# CPLD.net
KiCad netlist of a schematic drawn in Altium Designer
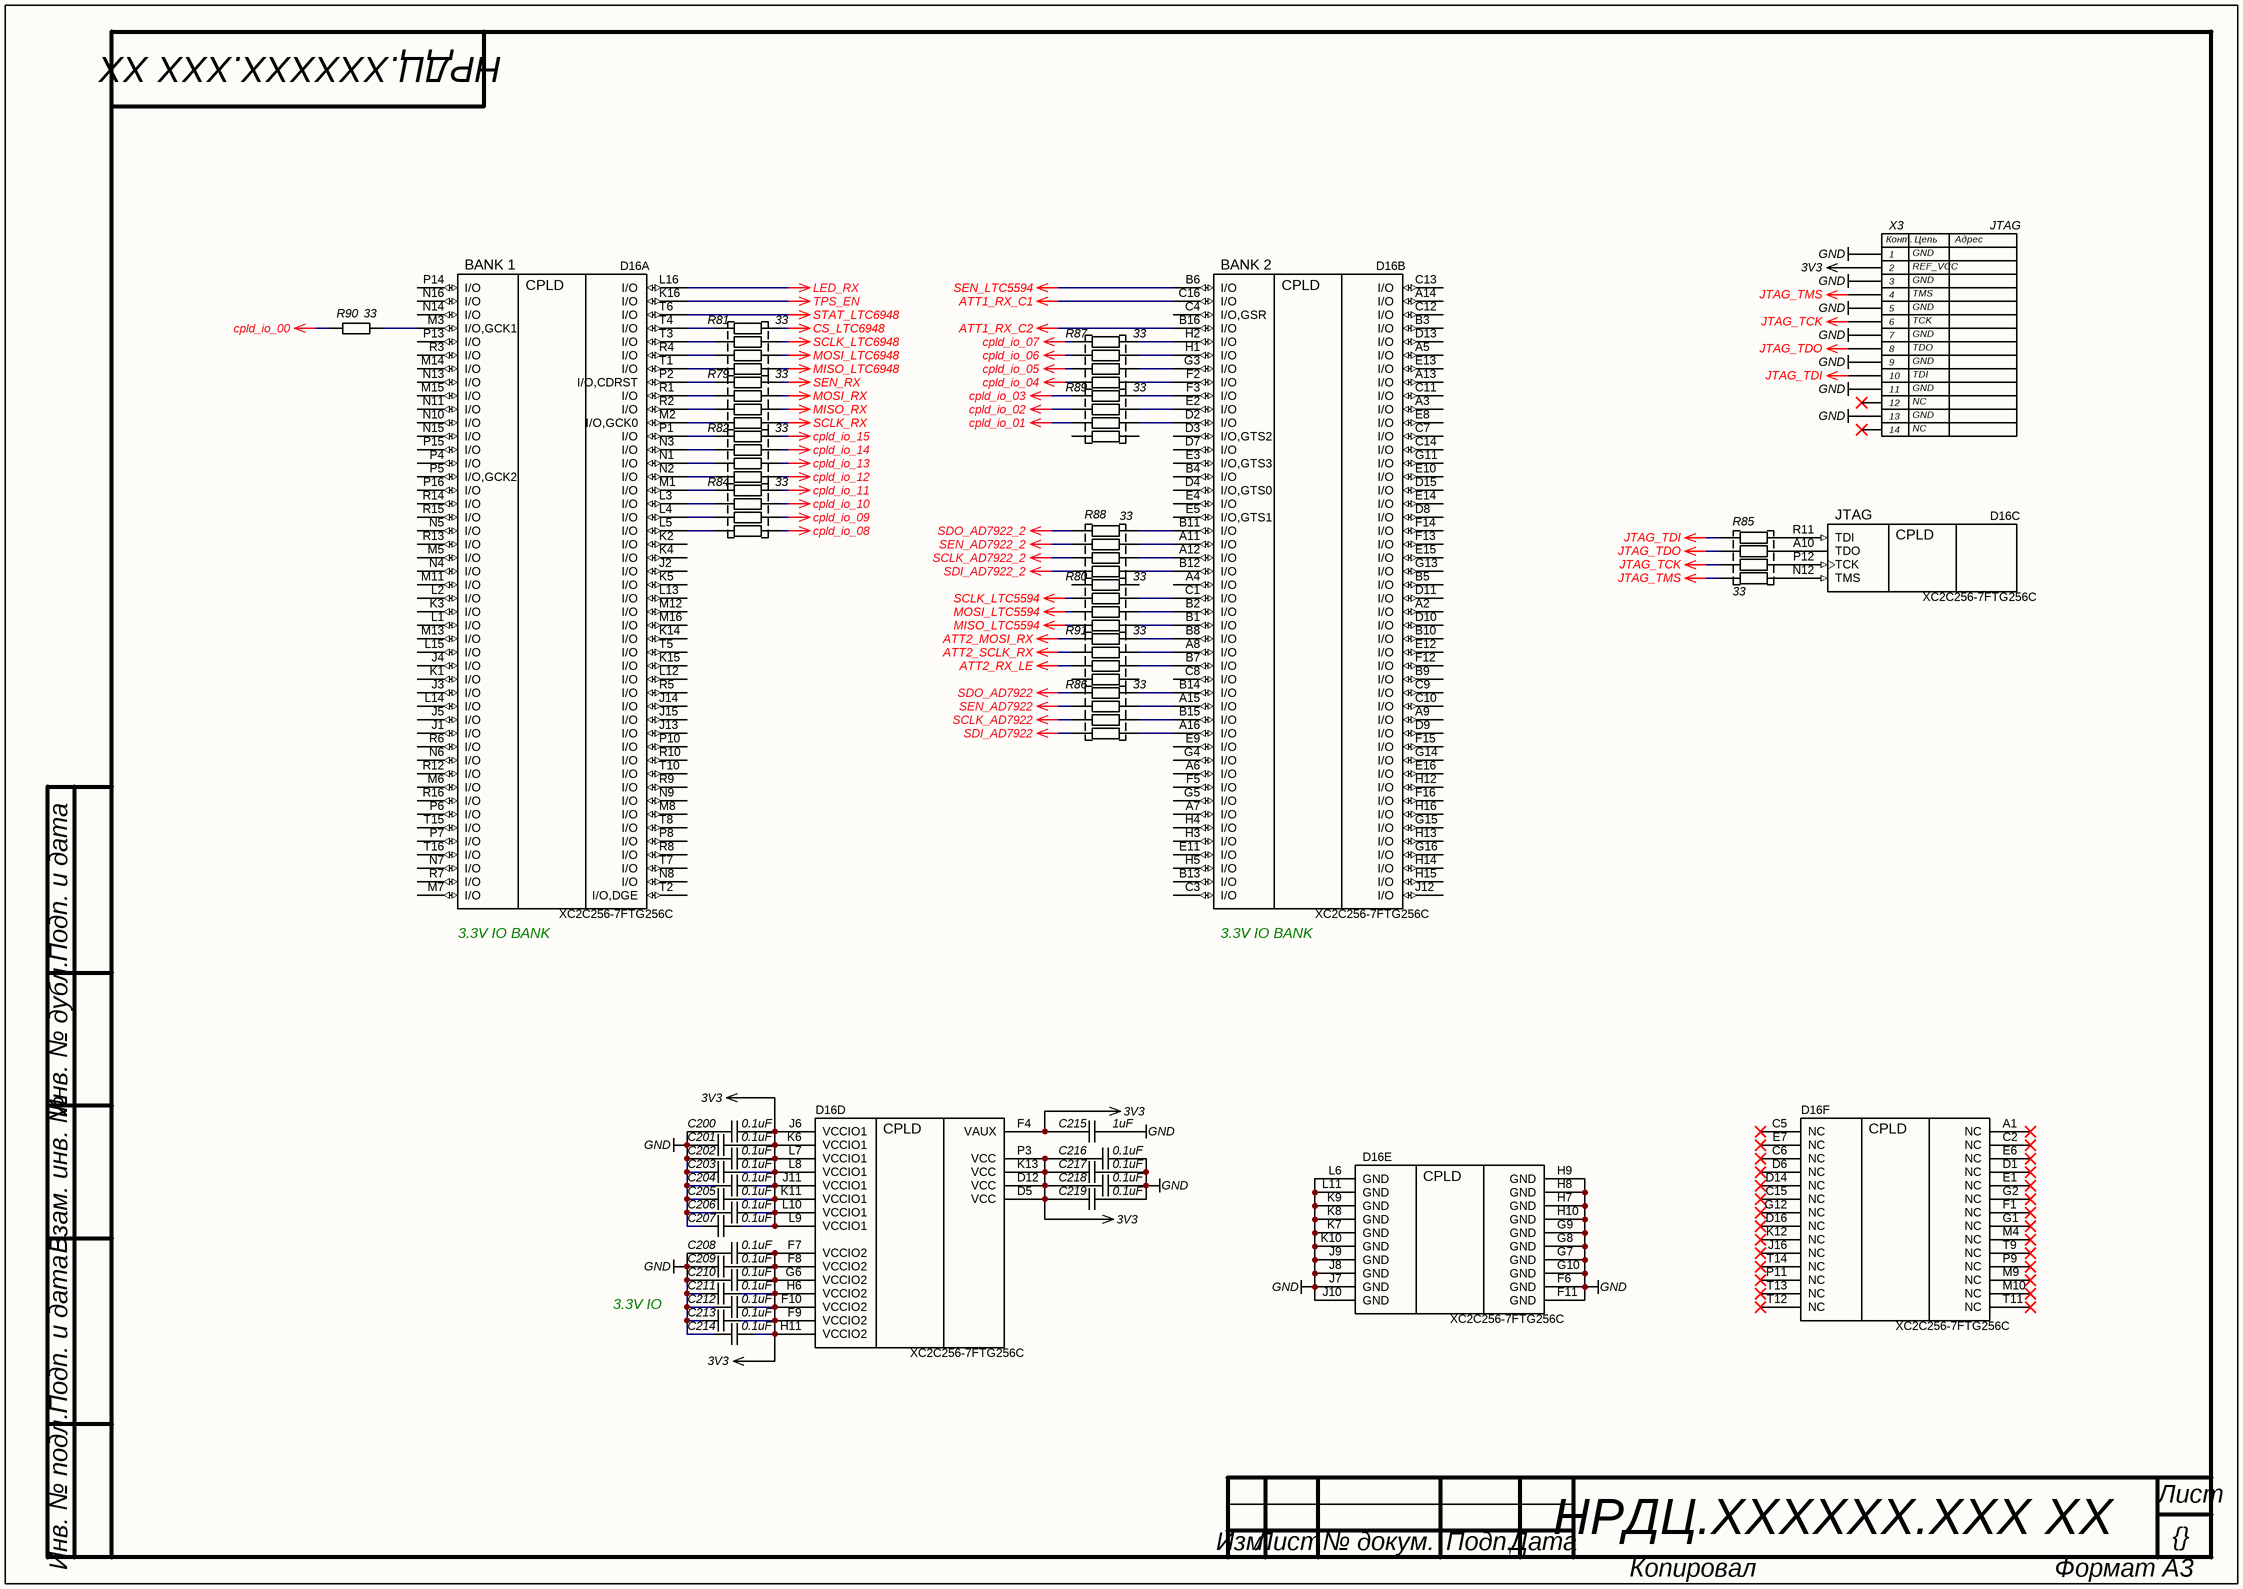
[diagram p0: CPLD.SchDoc]

(export (version "E")
  (design (tool "Eeschema 10.0.6"))
  (components
    (comp (ref "C200")
      (value "0.1uF")
      (footprint "C0402")
      (description "SMD Capacitor")
      (fields (field (name "MANUFACTURER") "Murata") (field (name "TOLERANCE") "10%"))
      (libsource (lib "Kintex_SDR") (part "CAP"))
    )
    (comp (ref "C201")
      (value "0.1uF")
      (footprint "C0402")
      (description "SMD Capacitor")
      (fields (field (name "MANUFACTURER") "Murata") (field (name "TOLERANCE") "10%"))
      (libsource (lib "Kintex_SDR") (part "CAP"))
    )
    (comp (ref "C202")
      (value "0.1uF")
      (footprint "C0402")
      (description "SMD Capacitor")
      (fields (field (name "MANUFACTURER") "Murata") (field (name "TOLERANCE") "10%"))
      (libsource (lib "Kintex_SDR") (part "CAP"))
    )
    (comp (ref "C203")
      (value "0.1uF")
      (footprint "C0402")
      (description "SMD Capacitor")
      (fields (field (name "MANUFACTURER") "Murata") (field (name "TOLERANCE") "10%"))
      (libsource (lib "Kintex_SDR") (part "CAP"))
    )
    (comp (ref "C204")
      (value "0.1uF")
      (footprint "C0402")
      (description "SMD Capacitor")
      (fields (field (name "MANUFACTURER") "Murata") (field (name "TOLERANCE") "10%"))
      (libsource (lib "Kintex_SDR") (part "CAP"))
    )
    (comp (ref "C205")
      (value "0.1uF")
      (footprint "C0402")
      (description "SMD Capacitor")
      (fields (field (name "MANUFACTURER") "Murata") (field (name "TOLERANCE") "10%"))
      (libsource (lib "Kintex_SDR") (part "CAP"))
    )
    (comp (ref "C206")
      (value "0.1uF")
      (footprint "C0402")
      (description "SMD Capacitor")
      (fields (field (name "MANUFACTURER") "Murata") (field (name "TOLERANCE") "10%"))
      (libsource (lib "Kintex_SDR") (part "CAP"))
    )
    (comp (ref "C207")
      (value "0.1uF")
      (footprint "C0402")
      (description "SMD Capacitor")
      (fields (field (name "MANUFACTURER") "Murata") (field (name "TOLERANCE") "10%"))
      (libsource (lib "Kintex_SDR") (part "CAP"))
    )
    (comp (ref "C208")
      (value "0.1uF")
      (footprint "C0402")
      (description "SMD Capacitor")
      (fields (field (name "MANUFACTURER") "Murata") (field (name "TOLERANCE") "10%"))
      (libsource (lib "Kintex_SDR") (part "CAP"))
    )
    (comp (ref "C209")
      (value "0.1uF")
      (footprint "C0402")
      (description "SMD Capacitor")
      (fields (field (name "MANUFACTURER") "Murata") (field (name "TOLERANCE") "10%"))
      (libsource (lib "Kintex_SDR") (part "CAP"))
    )
    (comp (ref "C210")
      (value "0.1uF")
      (footprint "C0402")
      (description "SMD Capacitor")
      (fields (field (name "MANUFACTURER") "Murata") (field (name "TOLERANCE") "10%"))
      (libsource (lib "Kintex_SDR") (part "CAP"))
    )
    (comp (ref "C211")
      (value "0.1uF")
      (footprint "C0402")
      (description "SMD Capacitor")
      (fields (field (name "MANUFACTURER") "Murata") (field (name "TOLERANCE") "10%"))
      (libsource (lib "Kintex_SDR") (part "CAP"))
    )
    (comp (ref "C212")
      (value "0.1uF")
      (footprint "C0402")
      (description "SMD Capacitor")
      (fields (field (name "MANUFACTURER") "Murata") (field (name "TOLERANCE") "10%"))
      (libsource (lib "Kintex_SDR") (part "CAP"))
    )
    (comp (ref "C213")
      (value "0.1uF")
      (footprint "C0402")
      (description "SMD Capacitor")
      (fields (field (name "MANUFACTURER") "Murata") (field (name "TOLERANCE") "10%"))
      (libsource (lib "Kintex_SDR") (part "CAP"))
    )
    (comp (ref "C214")
      (value "0.1uF")
      (footprint "C0402")
      (description "SMD Capacitor")
      (fields (field (name "MANUFACTURER") "Murata") (field (name "TOLERANCE") "10%"))
      (libsource (lib "Kintex_SDR") (part "CAP"))
    )
    (comp (ref "C215")
      (value "1uF")
      (footprint "C0402")
      (description "SMD Capacitor")
      (fields (field (name "MANUFACTURER") "Murata") (field (name "TOLERANCE") "10%"))
      (libsource (lib "Kintex_SDR") (part "CAP"))
    )
    (comp (ref "C216")
      (value "0.1uF")
      (footprint "C0402")
      (description "SMD Capacitor")
      (fields (field (name "MANUFACTURER") "Murata") (field (name "TOLERANCE") "10%"))
      (libsource (lib "Kintex_SDR") (part "CAP"))
    )
    (comp (ref "C217")
      (value "0.1uF")
      (footprint "C0402")
      (description "SMD Capacitor")
      (fields (field (name "MANUFACTURER") "Murata") (field (name "TOLERANCE") "10%"))
      (libsource (lib "Kintex_SDR") (part "CAP"))
    )
    (comp (ref "C218")
      (value "0.1uF")
      (footprint "C0402")
      (description "SMD Capacitor")
      (fields (field (name "MANUFACTURER") "Murata") (field (name "TOLERANCE") "10%"))
      (libsource (lib "Kintex_SDR") (part "CAP"))
    )
    (comp (ref "C219")
      (value "0.1uF")
      (footprint "C0402")
      (description "SMD Capacitor")
      (fields (field (name "MANUFACTURER") "Murata") (field (name "TOLERANCE") "10%"))
      (libsource (lib "Kintex_SDR") (part "CAP"))
    )
    (comp (ref "D16")
      (value "XC2C256-7FTG256C")
      (footprint "DBLib:FTG256")
      (description "CoolRunner-II 1.8V, 256 Macrocell CPLD, 184 User I/Os, 256-Ball FTBGA, Commercial Grade, Pb-Free")
      (libsource (lib "") (part "XC2C256-7FTG256C_1"))
    )
    (comp (ref "R79")
      (value "33")
      (footprint "EXN8V")
      (description "Chip Resistor Array")
      (fields (field (name "TOLERANCE") "5%") (field (name "MANUFACTURER") "Panasonic"))
      (libsource (lib "") (part "RES 4x0402_4"))
    )
    (comp (ref "R80")
      (value "33")
      (footprint "EXN8V")
      (description "Chip Resistor Array")
      (fields (field (name "TOLERANCE") "5%") (field (name "MANUFACTURER") "Panasonic"))
      (libsource (lib "") (part "RES 4x0402_1"))
    )
    (comp (ref "R81")
      (value "33")
      (footprint "EXN8V")
      (description "Chip Resistor Array")
      (fields (field (name "TOLERANCE") "5%") (field (name "MANUFACTURER") "Panasonic"))
      (libsource (lib "Kintex_SDR") (part "RES 4x0402"))
    )
    (comp (ref "R82")
      (value "33")
      (footprint "EXN8V")
      (description "Chip Resistor Array")
      (fields (field (name "TOLERANCE") "5%") (field (name "MANUFACTURER") "Panasonic"))
      (libsource (lib "") (part "RES 4x0402_3"))
    )
    (comp (ref "R84")
      (value "33")
      (footprint "EXN8V")
      (description "Chip Resistor Array")
      (fields (field (name "TOLERANCE") "5%") (field (name "MANUFACTURER") "Panasonic"))
      (libsource (lib "") (part "RES 4x0402_3"))
    )
    (comp (ref "R85")
      (value "33")
      (footprint "EXN8V")
      (description "Chip Resistor Array")
      (fields (field (name "TOLERANCE") "5%") (field (name "MANUFACTURER") "Panasonic"))
      (libsource (lib "") (part "RES 4x0402_1"))
    )
    (comp (ref "R86")
      (value "33")
      (footprint "EXN8V")
      (description "Chip Resistor Array")
      (fields (field (name "TOLERANCE") "5%") (field (name "MANUFACTURER") "Panasonic"))
      (libsource (lib "") (part "RES 4x0402_4"))
    )
    (comp (ref "R87")
      (value "33")
      (footprint "EXN8V")
      (description "Chip Resistor Array")
      (fields (field (name "TOLERANCE") "5%") (field (name "MANUFACTURER") "Panasonic"))
      (libsource (lib "") (part "RES 4x0402_1"))
    )
    (comp (ref "R88")
      (value "33")
      (footprint "EXN8V")
      (description "Chip Resistor Array")
      (fields (field (name "TOLERANCE") "5%") (field (name "MANUFACTURER") "Panasonic"))
      (libsource (lib "") (part "RES 4x0402_5"))
    )
    (comp (ref "R89")
      (value "33")
      (footprint "EXN8V")
      (description "Chip Resistor Array")
      (fields (field (name "TOLERANCE") "5%") (field (name "MANUFACTURER") "Panasonic"))
      (libsource (lib "") (part "RES 4x0402_1"))
    )
    (comp (ref "R90")
      (value "33")
      (footprint "R0402")
      (description "SMD Resistor")
      (fields (field (name "POWER") "0.2 Wt") (field (name "MANUFACTURER") "Panasonic Electronic Components"))
      (libsource (lib "Kintex_SDR") (part "RES"))
    )
    (comp (ref "R91")
      (value "33")
      (footprint "EXN8V")
      (description "Chip Resistor Array")
      (fields (field (name "TOLERANCE") "5%") (field (name "MANUFACTURER") "Panasonic"))
      (libsource (lib "") (part "RES 4x0402_2"))
    )
    (comp (ref "X3")
      (value "JTAG")
      (footprint "DBLib:JTAG Mail 2mm")
      (description "2.00mm Pitch, Milli-Grid PCB Header, Dual Row, Vertical, Through Hole, Shrouded, 14\r\nCircuits")
      (fields (field (name "MANUFACTURER") "Molex"))
      (libsource (lib "DBLib") (part "HDR Debug_14-pin"))
    )
  )
  (nets
    (net (code "1") (name "3V3") (class "Default")
      (node (ref "C200") (pin "2") (pinfunction "2_2") (pintype "passive"))
      (node (ref "C201") (pin "2") (pinfunction "2_2") (pintype "passive"))
      (node (ref "C202") (pin "2") (pinfunction "2_2") (pintype "passive"))
      (node (ref "C203") (pin "2") (pinfunction "2_2") (pintype "passive"))
      (node (ref "C204") (pin "2") (pinfunction "2_2") (pintype "passive"))
      (node (ref "C205") (pin "2") (pinfunction "2_2") (pintype "passive"))
      (node (ref "C206") (pin "2") (pinfunction "2_2") (pintype "passive"))
      (node (ref "C207") (pin "2") (pinfunction "2_2") (pintype "passive"))
      (node (ref "C208") (pin "2") (pinfunction "2_2") (pintype "passive"))
      (node (ref "C209") (pin "2") (pinfunction "2_2") (pintype "passive"))
      (node (ref "C210") (pin "2") (pinfunction "2_2") (pintype "passive"))
      (node (ref "C211") (pin "2") (pinfunction "2_2") (pintype "passive"))
      (node (ref "C212") (pin "2") (pinfunction "2_2") (pintype "passive"))
      (node (ref "C213") (pin "2") (pinfunction "2_2") (pintype "passive"))
      (node (ref "C214") (pin "2") (pinfunction "2_2") (pintype "passive"))
      (node (ref "C215") (pin "1") (pinfunction "1_1") (pintype "passive"))
      (node (ref "C216") (pin "1") (pinfunction "1_1") (pintype "passive"))
      (node (ref "C217") (pin "1") (pinfunction "1_1") (pintype "passive"))
      (node (ref "C218") (pin "1") (pinfunction "1_1") (pintype "passive"))
      (node (ref "C219") (pin "1") (pinfunction "1_1") (pintype "passive"))
      (node (ref "D16") (pin "D12") (pinfunction "VCC_D12") (pintype "power_in"))
      (node (ref "D16") (pin "D5") (pinfunction "VCC_D5") (pintype "power_in"))
      (node (ref "D16") (pin "F10") (pinfunction "VCCIO2_F10") (pintype "power_in"))
      (node (ref "D16") (pin "F4") (pinfunction "VAUX_F4") (pintype "power_in"))
      (node (ref "D16") (pin "F7") (pinfunction "VCCIO2_F7") (pintype "power_in"))
      (node (ref "D16") (pin "F8") (pinfunction "VCCIO2_F8") (pintype "power_in"))
      (node (ref "D16") (pin "F9") (pinfunction "VCCIO2_F9") (pintype "power_in"))
      (node (ref "D16") (pin "G6") (pinfunction "VCCIO2_G6") (pintype "power_in"))
      (node (ref "D16") (pin "H11") (pinfunction "VCCIO2_H11") (pintype "power_in"))
      (node (ref "D16") (pin "H6") (pinfunction "VCCIO2_H6") (pintype "power_in"))
      (node (ref "D16") (pin "J11") (pinfunction "VCCIO1_J11") (pintype "power_in"))
      (node (ref "D16") (pin "J6") (pinfunction "VCCIO1_J6") (pintype "power_in"))
      (node (ref "D16") (pin "K11") (pinfunction "VCCIO1_K11") (pintype "power_in"))
      (node (ref "D16") (pin "K13") (pinfunction "VCC_K13") (pintype "power_in"))
      (node (ref "D16") (pin "K6") (pinfunction "VCCIO1_K6") (pintype "power_in"))
      (node (ref "D16") (pin "L10") (pinfunction "VCCIO1_L10") (pintype "power_in"))
      (node (ref "D16") (pin "L7") (pinfunction "VCCIO1_L7") (pintype "power_in"))
      (node (ref "D16") (pin "L8") (pinfunction "VCCIO1_L8") (pintype "power_in"))
      (node (ref "D16") (pin "L9") (pinfunction "VCCIO1_L9") (pintype "power_in"))
      (node (ref "D16") (pin "P3") (pinfunction "VCC_P3") (pintype "power_in"))
      (node (ref "X3") (pin "2") (pinfunction "2_2") (pintype "passive"))
    )
    (net (code "2") (name "ATT1_RX_C1") (class "Default")
      (node (ref "D16") (pin "C16") (pinfunction "I/O_C16") (pintype "bidirectional"))
    )
    (net (code "3") (name "ATT1_RX_C2") (class "Default")
      (node (ref "D16") (pin "B16") (pinfunction "I/O_B16") (pintype "bidirectional"))
    )
    (net (code "4") (name "ATT2_MOSI_RX") (class "Default")
      (node (ref "R91") (pin "5") (pinfunction "5_5") (pintype "passive"))
    )
    (net (code "5") (name "ATT2_RX_LE") (class "Default")
      (node (ref "R91") (pin "7") (pinfunction "7_7") (pintype "passive"))
    )
    (net (code "6") (name "ATT2_SCLK_RX") (class "Default")
      (node (ref "R91") (pin "6") (pinfunction "6_6") (pintype "passive"))
    )
    (net (code "7") (name "CS_LTC6948") (class "Default")
      (node (ref "R81") (pin "8") (pinfunction "8_8") (pintype "passive"))
    )
    (net (code "8") (name "GND") (class "Default")
      (node (ref "C200") (pin "1") (pinfunction "1_1") (pintype "passive"))
      (node (ref "C201") (pin "1") (pinfunction "1_1") (pintype "passive"))
      (node (ref "C202") (pin "1") (pinfunction "1_1") (pintype "passive"))
      (node (ref "C203") (pin "1") (pinfunction "1_1") (pintype "passive"))
      (node (ref "C204") (pin "1") (pinfunction "1_1") (pintype "passive"))
      (node (ref "C205") (pin "1") (pinfunction "1_1") (pintype "passive"))
      (node (ref "C206") (pin "1") (pinfunction "1_1") (pintype "passive"))
      (node (ref "C207") (pin "1") (pinfunction "1_1") (pintype "passive"))
      (node (ref "C208") (pin "1") (pinfunction "1_1") (pintype "passive"))
      (node (ref "C209") (pin "1") (pinfunction "1_1") (pintype "passive"))
      (node (ref "C210") (pin "1") (pinfunction "1_1") (pintype "passive"))
      (node (ref "C211") (pin "1") (pinfunction "1_1") (pintype "passive"))
      (node (ref "C212") (pin "1") (pinfunction "1_1") (pintype "passive"))
      (node (ref "C213") (pin "1") (pinfunction "1_1") (pintype "passive"))
      (node (ref "C214") (pin "1") (pinfunction "1_1") (pintype "passive"))
      (node (ref "C215") (pin "2") (pinfunction "2_2") (pintype "passive"))
      (node (ref "C216") (pin "2") (pinfunction "2_2") (pintype "passive"))
      (node (ref "C217") (pin "2") (pinfunction "2_2") (pintype "passive"))
      (node (ref "C218") (pin "2") (pinfunction "2_2") (pintype "passive"))
      (node (ref "C219") (pin "2") (pinfunction "2_2") (pintype "passive"))
      (node (ref "D16") (pin "F11") (pinfunction "GND_F11") (pintype "power_in"))
      (node (ref "D16") (pin "F6") (pinfunction "GND_F6") (pintype "power_in"))
      (node (ref "D16") (pin "G10") (pinfunction "GND_G10") (pintype "power_in"))
      (node (ref "D16") (pin "G7") (pinfunction "GND_G7") (pintype "power_in"))
      (node (ref "D16") (pin "G8") (pinfunction "GND_G8") (pintype "power_in"))
      (node (ref "D16") (pin "G9") (pinfunction "GND_G9") (pintype "power_in"))
      (node (ref "D16") (pin "H10") (pinfunction "GND_H10") (pintype "power_in"))
      (node (ref "D16") (pin "H7") (pinfunction "GND_H7") (pintype "power_in"))
      (node (ref "D16") (pin "H8") (pinfunction "GND_H8") (pintype "power_in"))
      (node (ref "D16") (pin "H9") (pinfunction "GND_H9") (pintype "power_in"))
      (node (ref "D16") (pin "J10") (pinfunction "GND_J10") (pintype "power_in"))
      (node (ref "D16") (pin "J7") (pinfunction "GND_J7") (pintype "power_in"))
      (node (ref "D16") (pin "J8") (pinfunction "GND_J8") (pintype "power_in"))
      (node (ref "D16") (pin "J9") (pinfunction "GND_J9") (pintype "power_in"))
      (node (ref "D16") (pin "K10") (pinfunction "GND_K10") (pintype "power_in"))
      (node (ref "D16") (pin "K7") (pinfunction "GND_K7") (pintype "power_in"))
      (node (ref "D16") (pin "K8") (pinfunction "GND_K8") (pintype "power_in"))
      (node (ref "D16") (pin "K9") (pinfunction "GND_K9") (pintype "power_in"))
      (node (ref "D16") (pin "L11") (pinfunction "GND_L11") (pintype "power_in"))
      (node (ref "D16") (pin "L6") (pinfunction "GND_L6") (pintype "power_in"))
      (node (ref "X3") (pin "1") (pinfunction "1_1") (pintype "passive"))
      (node (ref "X3") (pin "11") (pinfunction "11_11") (pintype "passive"))
      (node (ref "X3") (pin "13") (pinfunction "13_13") (pintype "passive"))
      (node (ref "X3") (pin "3") (pinfunction "3_3") (pintype "passive"))
      (node (ref "X3") (pin "5") (pinfunction "5_5") (pintype "passive"))
      (node (ref "X3") (pin "7") (pinfunction "7_7") (pintype "passive"))
      (node (ref "X3") (pin "9") (pinfunction "9_9") (pintype "passive"))
    )
    (net (code "9") (name "JTAG_TCK") (class "Default")
      (node (ref "R85") (pin "6") (pinfunction "6_6") (pintype "passive"))
      (node (ref "X3") (pin "6") (pinfunction "6_6") (pintype "passive"))
    )
    (net (code "10") (name "JTAG_TDI") (class "Default")
      (node (ref "R85") (pin "8") (pinfunction "8_8") (pintype "passive"))
      (node (ref "X3") (pin "10") (pinfunction "10_10") (pintype "passive"))
    )
    (net (code "11") (name "JTAG_TDO") (class "Default")
      (node (ref "R85") (pin "7") (pinfunction "7_7") (pintype "passive"))
      (node (ref "X3") (pin "8") (pinfunction "8_8") (pintype "passive"))
    )
    (net (code "12") (name "JTAG_TMS") (class "Default")
      (node (ref "R85") (pin "5") (pinfunction "5_5") (pintype "passive"))
      (node (ref "X3") (pin "4") (pinfunction "4_4") (pintype "passive"))
    )
    (net (code "13") (name "LED_RX") (class "Default")
      (node (ref "D16") (pin "L16") (pinfunction "I/O_L16") (pintype "bidirectional"))
    )
    (net (code "14") (name "MISO_LTC5594") (class "Default")
      (node (ref "R80") (pin "5") (pinfunction "5_5") (pintype "passive"))
    )
    (net (code "15") (name "MISO_LTC6948") (class "Default")
      (node (ref "R81") (pin "5") (pinfunction "5_5") (pintype "passive"))
    )
    (net (code "16") (name "MISO_RX") (class "Default")
      (node (ref "R79") (pin "7") (pinfunction "7_7") (pintype "passive"))
    )
    (net (code "17") (name "MOSI_LTC5594") (class "Default")
      (node (ref "R80") (pin "6") (pinfunction "6_6") (pintype "passive"))
    )
    (net (code "18") (name "MOSI_LTC6948") (class "Default")
      (node (ref "R81") (pin "6") (pinfunction "6_6") (pintype "passive"))
    )
    (net (code "19") (name "MOSI_RX") (class "Default")
      (node (ref "R79") (pin "6") (pinfunction "6_6") (pintype "passive"))
    )
    (net (code "20") (name "Net-(D16A-I{slash}O,CDRST)") (class "Default")
      (node (ref "D16") (pin "P2") (pinfunction "I/O,CDRST_P2") (pintype "bidirectional"))
      (node (ref "R79") (pin "4") (pinfunction "4_4") (pintype "passive"))
    )
    (net (code "21") (name "Net-(D16A-I{slash}O,GCK0)") (class "Default")
      (node (ref "D16") (pin "M2") (pinfunction "I/O,GCK0_M2") (pintype "bidirectional"))
      (node (ref "R79") (pin "1") (pinfunction "1_1") (pintype "passive"))
    )
    (net (code "22") (name "Net-(D16A-I{slash}O,GCK1)") (class "Default")
      (node (ref "D16") (pin "M3") (pinfunction "I/O,GCK1_M3") (pintype "bidirectional"))
      (node (ref "R90") (pin "1") (pinfunction "1_1") (pintype "passive"))
    )
    (net (code "23") (name "Net-(D16A-I{slash}O-PadL3)") (class "Default")
      (node (ref "D16") (pin "L3") (pinfunction "I/O_L3") (pintype "bidirectional"))
      (node (ref "R84") (pin "2") (pinfunction "2_2") (pintype "passive"))
    )
    (net (code "24") (name "Net-(D16A-I{slash}O-PadL4)") (class "Default")
      (node (ref "D16") (pin "L4") (pinfunction "I/O_L4") (pintype "bidirectional"))
      (node (ref "R84") (pin "3") (pinfunction "3_3") (pintype "passive"))
    )
    (net (code "25") (name "Net-(D16A-I{slash}O-PadL5)") (class "Default")
      (node (ref "D16") (pin "L5") (pinfunction "I/O_L5") (pintype "bidirectional"))
      (node (ref "R84") (pin "4") (pinfunction "4_4") (pintype "passive"))
    )
    (net (code "26") (name "Net-(D16A-I{slash}O-PadM1)") (class "Default")
      (node (ref "D16") (pin "M1") (pinfunction "I/O_M1") (pintype "bidirectional"))
      (node (ref "R84") (pin "1") (pinfunction "1_1") (pintype "passive"))
    )
    (net (code "27") (name "Net-(D16A-I{slash}O-PadN1)") (class "Default")
      (node (ref "D16") (pin "N1") (pinfunction "I/O_N1") (pintype "bidirectional"))
      (node (ref "R82") (pin "3") (pinfunction "3_3") (pintype "passive"))
    )
    (net (code "28") (name "Net-(D16A-I{slash}O-PadN2)") (class "Default")
      (node (ref "D16") (pin "N2") (pinfunction "I/O_N2") (pintype "bidirectional"))
      (node (ref "R82") (pin "4") (pinfunction "4_4") (pintype "passive"))
    )
    (net (code "29") (name "Net-(D16A-I{slash}O-PadN3)") (class "Default")
      (node (ref "D16") (pin "N3") (pinfunction "I/O_N3") (pintype "bidirectional"))
      (node (ref "R82") (pin "2") (pinfunction "2_2") (pintype "passive"))
    )
    (net (code "30") (name "Net-(D16A-I{slash}O-PadP1)") (class "Default")
      (node (ref "D16") (pin "P1") (pinfunction "I/O_P1") (pintype "bidirectional"))
      (node (ref "R82") (pin "1") (pinfunction "1_1") (pintype "passive"))
    )
    (net (code "31") (name "Net-(D16A-I{slash}O-PadR1)") (class "Default")
      (node (ref "D16") (pin "R1") (pinfunction "I/O_R1") (pintype "bidirectional"))
      (node (ref "R79") (pin "3") (pinfunction "3_3") (pintype "passive"))
    )
    (net (code "32") (name "Net-(D16A-I{slash}O-PadR2)") (class "Default")
      (node (ref "D16") (pin "R2") (pinfunction "I/O_R2") (pintype "bidirectional"))
      (node (ref "R79") (pin "2") (pinfunction "2_2") (pintype "passive"))
    )
    (net (code "33") (name "Net-(D16A-I{slash}O-PadR4)") (class "Default")
      (node (ref "D16") (pin "R4") (pinfunction "I/O_R4") (pintype "bidirectional"))
      (node (ref "R81") (pin "2") (pinfunction "2_2") (pintype "passive"))
    )
    (net (code "34") (name "Net-(D16A-I{slash}O-PadT1)") (class "Default")
      (node (ref "D16") (pin "T1") (pinfunction "I/O_T1") (pintype "bidirectional"))
      (node (ref "R81") (pin "4") (pinfunction "4_4") (pintype "passive"))
    )
    (net (code "35") (name "Net-(D16A-I{slash}O-PadT3)") (class "Default")
      (node (ref "D16") (pin "T3") (pinfunction "I/O_T3") (pintype "bidirectional"))
      (node (ref "R81") (pin "3") (pinfunction "3_3") (pintype "passive"))
    )
    (net (code "36") (name "Net-(D16A-I{slash}O-PadT4)") (class "Default")
      (node (ref "D16") (pin "T4") (pinfunction "I/O_T4") (pintype "bidirectional"))
      (node (ref "R81") (pin "1") (pinfunction "1_1") (pintype "passive"))
    )
    (net (code "37") (name "Net-(D16B-I{slash}O-PadA8)") (class "Default")
      (node (ref "D16") (pin "A8") (pinfunction "I/O_A8") (pintype "bidirectional"))
      (node (ref "R91") (pin "3") (pinfunction "3_3") (pintype "passive"))
    )
    (net (code "38") (name "Net-(D16B-I{slash}O-PadA11)") (class "Default")
      (node (ref "D16") (pin "A11") (pinfunction "I/O_A11") (pintype "bidirectional"))
      (node (ref "R88") (pin "1") (pinfunction "1_1") (pintype "passive"))
    )
    (net (code "39") (name "Net-(D16B-I{slash}O-PadA12)") (class "Default")
      (node (ref "D16") (pin "A12") (pinfunction "I/O_A12") (pintype "bidirectional"))
      (node (ref "R88") (pin "3") (pinfunction "3_3") (pintype "passive"))
    )
    (net (code "40") (name "Net-(D16B-I{slash}O-PadA15)") (class "Default")
      (node (ref "D16") (pin "A15") (pinfunction "I/O_A15") (pintype "bidirectional"))
      (node (ref "R86") (pin "6") (pinfunction "6_6") (pintype "passive"))
    )
    (net (code "41") (name "Net-(D16B-I{slash}O-PadA16)") (class "Default")
      (node (ref "D16") (pin "A16") (pinfunction "I/O_A16") (pintype "bidirectional"))
      (node (ref "R86") (pin "8") (pinfunction "8_8") (pintype "passive"))
    )
    (net (code "42") (name "Net-(D16B-I{slash}O-PadB1)") (class "Default")
      (node (ref "D16") (pin "B1") (pinfunction "I/O_B1") (pintype "bidirectional"))
      (node (ref "R80") (pin "4") (pinfunction "4_4") (pintype "passive"))
    )
    (net (code "43") (name "Net-(D16B-I{slash}O-PadB2)") (class "Default")
      (node (ref "D16") (pin "B2") (pinfunction "I/O_B2") (pintype "bidirectional"))
      (node (ref "R80") (pin "3") (pinfunction "3_3") (pintype "passive"))
    )
    (net (code "44") (name "Net-(D16B-I{slash}O-PadB7)") (class "Default")
      (node (ref "D16") (pin "B7") (pinfunction "I/O_B7") (pintype "bidirectional"))
      (node (ref "R91") (pin "2") (pinfunction "2_2") (pintype "passive"))
    )
    (net (code "45") (name "Net-(D16B-I{slash}O-PadB8)") (class "Default")
      (node (ref "D16") (pin "B8") (pinfunction "I/O_B8") (pintype "bidirectional"))
      (node (ref "R91") (pin "4") (pinfunction "4_4") (pintype "passive"))
    )
    (net (code "46") (name "Net-(D16B-I{slash}O-PadB11)") (class "Default")
      (node (ref "D16") (pin "B11") (pinfunction "I/O_B11") (pintype "bidirectional"))
      (node (ref "R88") (pin "2") (pinfunction "2_2") (pintype "passive"))
    )
    (net (code "47") (name "Net-(D16B-I{slash}O-PadB12)") (class "Default")
      (node (ref "D16") (pin "B12") (pinfunction "I/O_B12") (pintype "bidirectional"))
      (node (ref "R88") (pin "4") (pinfunction "4_4") (pintype "passive"))
    )
    (net (code "48") (name "Net-(D16B-I{slash}O-PadB14)") (class "Default")
      (node (ref "D16") (pin "B14") (pinfunction "I/O_B14") (pintype "bidirectional"))
      (node (ref "R86") (pin "5") (pinfunction "5_5") (pintype "passive"))
    )
    (net (code "49") (name "Net-(D16B-I{slash}O-PadB15)") (class "Default")
      (node (ref "D16") (pin "B15") (pinfunction "I/O_B15") (pintype "bidirectional"))
      (node (ref "R86") (pin "7") (pinfunction "7_7") (pintype "passive"))
    )
    (net (code "50") (name "Net-(D16B-I{slash}O-PadC1)") (class "Default")
      (node (ref "D16") (pin "C1") (pinfunction "I/O_C1") (pintype "bidirectional"))
      (node (ref "R80") (pin "2") (pinfunction "2_2") (pintype "passive"))
    )
    (net (code "51") (name "Net-(D16B-I{slash}O-PadD2)") (class "Default")
      (node (ref "D16") (pin "D2") (pinfunction "I/O_D2") (pintype "bidirectional"))
      (node (ref "R89") (pin "3") (pinfunction "3_3") (pintype "passive"))
    )
    (net (code "52") (name "Net-(D16B-I{slash}O-PadE2)") (class "Default")
      (node (ref "D16") (pin "E2") (pinfunction "I/O_E2") (pintype "bidirectional"))
      (node (ref "R89") (pin "2") (pinfunction "2_2") (pintype "passive"))
    )
    (net (code "53") (name "Net-(D16B-I{slash}O-PadF2)") (class "Default")
      (node (ref "D16") (pin "F2") (pinfunction "I/O_F2") (pintype "bidirectional"))
      (node (ref "R87") (pin "4") (pinfunction "4_4") (pintype "passive"))
    )
    (net (code "54") (name "Net-(D16B-I{slash}O-PadF3)") (class "Default")
      (node (ref "D16") (pin "F3") (pinfunction "I/O_F3") (pintype "bidirectional"))
      (node (ref "R89") (pin "1") (pinfunction "1_1") (pintype "passive"))
    )
    (net (code "55") (name "Net-(D16B-I{slash}O-PadG3)") (class "Default")
      (node (ref "D16") (pin "G3") (pinfunction "I/O_G3") (pintype "bidirectional"))
      (node (ref "R87") (pin "3") (pinfunction "3_3") (pintype "passive"))
    )
    (net (code "56") (name "Net-(D16B-I{slash}O-PadH1)") (class "Default")
      (node (ref "D16") (pin "H1") (pinfunction "I/O_H1") (pintype "bidirectional"))
      (node (ref "R87") (pin "2") (pinfunction "2_2") (pintype "passive"))
    )
    (net (code "57") (name "Net-(D16B-I{slash}O-PadH2)") (class "Default")
      (node (ref "D16") (pin "H2") (pinfunction "I/O_H2") (pintype "bidirectional"))
      (node (ref "R87") (pin "1") (pinfunction "1_1") (pintype "passive"))
    )
    (net (code "58") (name "Net-(D16C-TCK)") (class "Default")
      (node (ref "D16") (pin "P12") (pinfunction "TCK_P12") (pintype "input"))
      (node (ref "R85") (pin "3") (pinfunction "3_3") (pintype "passive"))
    )
    (net (code "59") (name "Net-(D16C-TDI)") (class "Default")
      (node (ref "D16") (pin "R11") (pinfunction "TDI_R11") (pintype "input"))
      (node (ref "R85") (pin "1") (pinfunction "1_1") (pintype "passive"))
    )
    (net (code "60") (name "Net-(D16C-TDO)") (class "Default")
      (node (ref "D16") (pin "A10") (pinfunction "TDO_A10") (pintype "passive"))
      (node (ref "R85") (pin "2") (pinfunction "2_2") (pintype "passive"))
    )
    (net (code "61") (name "Net-(D16C-TMS)") (class "Default")
      (node (ref "D16") (pin "N12") (pinfunction "TMS_N12") (pintype "input"))
      (node (ref "R85") (pin "4") (pinfunction "4_4") (pintype "passive"))
    )
    (net (code "62") (name "SCLK_AD7922") (class "Default")
      (node (ref "R86") (pin "2") (pinfunction "2_2") (pintype "passive"))
    )
    (net (code "63") (name "SCLK_AD7922_2") (class "Default")
      (node (ref "R88") (pin "6") (pinfunction "6_6") (pintype "passive"))
    )
    (net (code "64") (name "SCLK_LTC5594") (class "Default")
      (node (ref "R80") (pin "7") (pinfunction "7_7") (pintype "passive"))
    )
    (net (code "65") (name "SCLK_LTC6948") (class "Default")
      (node (ref "R81") (pin "7") (pinfunction "7_7") (pintype "passive"))
    )
    (net (code "66") (name "SCLK_RX") (class "Default")
      (node (ref "R79") (pin "8") (pinfunction "8_8") (pintype "passive"))
    )
    (net (code "67") (name "SDI_AD7922") (class "Default")
      (node (ref "R86") (pin "1") (pinfunction "1_1") (pintype "passive"))
    )
    (net (code "68") (name "SDI_AD7922_2") (class "Default")
      (node (ref "R88") (pin "5") (pinfunction "5_5") (pintype "passive"))
    )
    (net (code "69") (name "SDO_AD7922") (class "Default")
      (node (ref "R86") (pin "4") (pinfunction "4_4") (pintype "passive"))
    )
    (net (code "70") (name "SDO_AD7922_2") (class "Default")
      (node (ref "R88") (pin "8") (pinfunction "8_8") (pintype "passive"))
    )
    (net (code "71") (name "SEN_AD7922") (class "Default")
      (node (ref "R86") (pin "3") (pinfunction "3_3") (pintype "passive"))
    )
    (net (code "72") (name "SEN_AD7922_2") (class "Default")
      (node (ref "R88") (pin "7") (pinfunction "7_7") (pintype "passive"))
    )
    (net (code "73") (name "SEN_LTC5594") (class "Default")
      (node (ref "D16") (pin "B6") (pinfunction "I/O_B6") (pintype "bidirectional"))
    )
    (net (code "74") (name "SEN_RX") (class "Default")
      (node (ref "R79") (pin "5") (pinfunction "5_5") (pintype "passive"))
    )
    (net (code "75") (name "STAT_LTC6948") (class "Default")
      (node (ref "D16") (pin "T6") (pinfunction "I/O_T6") (pintype "bidirectional"))
    )
    (net (code "76") (name "TPS_EN") (class "Default")
      (node (ref "D16") (pin "K16") (pinfunction "I/O_K16") (pintype "bidirectional"))
    )
    (net (code "77") (name "cpld_io_00") (class "Default")
      (node (ref "R90") (pin "2") (pinfunction "2_2") (pintype "passive"))
    )
    (net (code "78") (name "cpld_io_01") (class "Default")
      (node (ref "R89") (pin "6") (pinfunction "6_6") (pintype "passive"))
    )
    (net (code "79") (name "cpld_io_02") (class "Default")
      (node (ref "R89") (pin "7") (pinfunction "7_7") (pintype "passive"))
    )
    (net (code "80") (name "cpld_io_03") (class "Default")
      (node (ref "R89") (pin "8") (pinfunction "8_8") (pintype "passive"))
    )
    (net (code "81") (name "cpld_io_04") (class "Default")
      (node (ref "R87") (pin "5") (pinfunction "5_5") (pintype "passive"))
    )
    (net (code "82") (name "cpld_io_05") (class "Default")
      (node (ref "R87") (pin "6") (pinfunction "6_6") (pintype "passive"))
    )
    (net (code "83") (name "cpld_io_06") (class "Default")
      (node (ref "R87") (pin "7") (pinfunction "7_7") (pintype "passive"))
    )
    (net (code "84") (name "cpld_io_07") (class "Default")
      (node (ref "R87") (pin "8") (pinfunction "8_8") (pintype "passive"))
    )
    (net (code "85") (name "cpld_io_08") (class "Default")
      (node (ref "R84") (pin "5") (pinfunction "5_5") (pintype "passive"))
    )
    (net (code "86") (name "cpld_io_09") (class "Default")
      (node (ref "R84") (pin "6") (pinfunction "6_6") (pintype "passive"))
    )
    (net (code "87") (name "cpld_io_10") (class "Default")
      (node (ref "R84") (pin "7") (pinfunction "7_7") (pintype "passive"))
    )
    (net (code "88") (name "cpld_io_11") (class "Default")
      (node (ref "R84") (pin "8") (pinfunction "8_8") (pintype "passive"))
    )
    (net (code "89") (name "cpld_io_12") (class "Default")
      (node (ref "R82") (pin "5") (pinfunction "5_5") (pintype "passive"))
    )
    (net (code "90") (name "cpld_io_13") (class "Default")
      (node (ref "R82") (pin "6") (pinfunction "6_6") (pintype "passive"))
    )
    (net (code "91") (name "cpld_io_14") (class "Default")
      (node (ref "R82") (pin "7") (pinfunction "7_7") (pintype "passive"))
    )
    (net (code "92") (name "cpld_io_15") (class "Default")
      (node (ref "R82") (pin "8") (pinfunction "8_8") (pintype "passive"))
    )
    (net (code "93") (name "unconnected-(D16A-I{slash}O,DGE-PadT2)") (class "Default")
      (node (ref "D16") (pin "T2") (pinfunction "I/O,DGE_T2") (pintype "bidirectional"))
    )
    (net (code "94") (name "unconnected-(D16A-I{slash}O,GCK2-PadP5)") (class "Default")
      (node (ref "D16") (pin "P5") (pinfunction "I/O,GCK2_P5") (pintype "bidirectional"))
    )
    (net (code "95") (name "unconnected-(D16A-I{slash}O-PadJ1)") (class "Default")
      (node (ref "D16") (pin "J1") (pinfunction "I/O_J1") (pintype "bidirectional"))
    )
    (net (code "96") (name "unconnected-(D16A-I{slash}O-PadJ2)") (class "Default")
      (node (ref "D16") (pin "J2") (pinfunction "I/O_J2") (pintype "bidirectional"))
    )
    (net (code "97") (name "unconnected-(D16A-I{slash}O-PadJ3)") (class "Default")
      (node (ref "D16") (pin "J3") (pinfunction "I/O_J3") (pintype "bidirectional"))
    )
    (net (code "98") (name "unconnected-(D16A-I{slash}O-PadJ4)") (class "Default")
      (node (ref "D16") (pin "J4") (pinfunction "I/O_J4") (pintype "bidirectional"))
    )
    (net (code "99") (name "unconnected-(D16A-I{slash}O-PadJ5)") (class "Default")
      (node (ref "D16") (pin "J5") (pinfunction "I/O_J5") (pintype "bidirectional"))
    )
    (net (code "100") (name "unconnected-(D16A-I{slash}O-PadJ13)") (class "Default")
      (node (ref "D16") (pin "J13") (pinfunction "I/O_J13") (pintype "bidirectional"))
    )
    (net (code "101") (name "unconnected-(D16A-I{slash}O-PadJ14)") (class "Default")
      (node (ref "D16") (pin "J14") (pinfunction "I/O_J14") (pintype "bidirectional"))
    )
    (net (code "102") (name "unconnected-(D16A-I{slash}O-PadJ15)") (class "Default")
      (node (ref "D16") (pin "J15") (pinfunction "I/O_J15") (pintype "bidirectional"))
    )
    (net (code "103") (name "unconnected-(D16A-I{slash}O-PadK1)") (class "Default")
      (node (ref "D16") (pin "K1") (pinfunction "I/O_K1") (pintype "bidirectional"))
    )
    (net (code "104") (name "unconnected-(D16A-I{slash}O-PadK2)") (class "Default")
      (node (ref "D16") (pin "K2") (pinfunction "I/O_K2") (pintype "bidirectional"))
    )
    (net (code "105") (name "unconnected-(D16A-I{slash}O-PadK3)") (class "Default")
      (node (ref "D16") (pin "K3") (pinfunction "I/O_K3") (pintype "bidirectional"))
    )
    (net (code "106") (name "unconnected-(D16A-I{slash}O-PadK4)") (class "Default")
      (node (ref "D16") (pin "K4") (pinfunction "I/O_K4") (pintype "bidirectional"))
    )
    (net (code "107") (name "unconnected-(D16A-I{slash}O-PadK5)") (class "Default")
      (node (ref "D16") (pin "K5") (pinfunction "I/O_K5") (pintype "bidirectional"))
    )
    (net (code "108") (name "unconnected-(D16A-I{slash}O-PadK14)") (class "Default")
      (node (ref "D16") (pin "K14") (pinfunction "I/O_K14") (pintype "bidirectional"))
    )
    (net (code "109") (name "unconnected-(D16A-I{slash}O-PadK15)") (class "Default")
      (node (ref "D16") (pin "K15") (pinfunction "I/O_K15") (pintype "bidirectional"))
    )
    (net (code "110") (name "unconnected-(D16A-I{slash}O-PadL1)") (class "Default")
      (node (ref "D16") (pin "L1") (pinfunction "I/O_L1") (pintype "bidirectional"))
    )
    (net (code "111") (name "unconnected-(D16A-I{slash}O-PadL2)") (class "Default")
      (node (ref "D16") (pin "L2") (pinfunction "I/O_L2") (pintype "bidirectional"))
    )
    (net (code "112") (name "unconnected-(D16A-I{slash}O-PadL12)") (class "Default")
      (node (ref "D16") (pin "L12") (pinfunction "I/O_L12") (pintype "bidirectional"))
    )
    (net (code "113") (name "unconnected-(D16A-I{slash}O-PadL13)") (class "Default")
      (node (ref "D16") (pin "L13") (pinfunction "I/O_L13") (pintype "bidirectional"))
    )
    (net (code "114") (name "unconnected-(D16A-I{slash}O-PadL14)") (class "Default")
      (node (ref "D16") (pin "L14") (pinfunction "I/O_L14") (pintype "bidirectional"))
    )
    (net (code "115") (name "unconnected-(D16A-I{slash}O-PadL15)") (class "Default")
      (node (ref "D16") (pin "L15") (pinfunction "I/O_L15") (pintype "bidirectional"))
    )
    (net (code "116") (name "unconnected-(D16A-I{slash}O-PadM5)") (class "Default")
      (node (ref "D16") (pin "M5") (pinfunction "I/O_M5") (pintype "bidirectional"))
    )
    (net (code "117") (name "unconnected-(D16A-I{slash}O-PadM6)") (class "Default")
      (node (ref "D16") (pin "M6") (pinfunction "I/O_M6") (pintype "bidirectional"))
    )
    (net (code "118") (name "unconnected-(D16A-I{slash}O-PadM7)") (class "Default")
      (node (ref "D16") (pin "M7") (pinfunction "I/O_M7") (pintype "bidirectional"))
    )
    (net (code "119") (name "unconnected-(D16A-I{slash}O-PadM8)") (class "Default")
      (node (ref "D16") (pin "M8") (pinfunction "I/O_M8") (pintype "bidirectional"))
    )
    (net (code "120") (name "unconnected-(D16A-I{slash}O-PadM11)") (class "Default")
      (node (ref "D16") (pin "M11") (pinfunction "I/O_M11") (pintype "bidirectional"))
    )
    (net (code "121") (name "unconnected-(D16A-I{slash}O-PadM12)") (class "Default")
      (node (ref "D16") (pin "M12") (pinfunction "I/O_M12") (pintype "bidirectional"))
    )
    (net (code "122") (name "unconnected-(D16A-I{slash}O-PadM13)") (class "Default")
      (node (ref "D16") (pin "M13") (pinfunction "I/O_M13") (pintype "bidirectional"))
    )
    (net (code "123") (name "unconnected-(D16A-I{slash}O-PadM14)") (class "Default")
      (node (ref "D16") (pin "M14") (pinfunction "I/O_M14") (pintype "bidirectional"))
    )
    (net (code "124") (name "unconnected-(D16A-I{slash}O-PadM15)") (class "Default")
      (node (ref "D16") (pin "M15") (pinfunction "I/O_M15") (pintype "bidirectional"))
    )
    (net (code "125") (name "unconnected-(D16A-I{slash}O-PadM16)") (class "Default")
      (node (ref "D16") (pin "M16") (pinfunction "I/O_M16") (pintype "bidirectional"))
    )
    (net (code "126") (name "unconnected-(D16A-I{slash}O-PadN4)") (class "Default")
      (node (ref "D16") (pin "N4") (pinfunction "I/O_N4") (pintype "bidirectional"))
    )
    (net (code "127") (name "unconnected-(D16A-I{slash}O-PadN5)") (class "Default")
      (node (ref "D16") (pin "N5") (pinfunction "I/O_N5") (pintype "bidirectional"))
    )
    (net (code "128") (name "unconnected-(D16A-I{slash}O-PadN6)") (class "Default")
      (node (ref "D16") (pin "N6") (pinfunction "I/O_N6") (pintype "bidirectional"))
    )
    (net (code "129") (name "unconnected-(D16A-I{slash}O-PadN7)") (class "Default")
      (node (ref "D16") (pin "N7") (pinfunction "I/O_N7") (pintype "bidirectional"))
    )
    (net (code "130") (name "unconnected-(D16A-I{slash}O-PadN8)") (class "Default")
      (node (ref "D16") (pin "N8") (pinfunction "I/O_N8") (pintype "bidirectional"))
    )
    (net (code "131") (name "unconnected-(D16A-I{slash}O-PadN9)") (class "Default")
      (node (ref "D16") (pin "N9") (pinfunction "I/O_N9") (pintype "bidirectional"))
    )
    (net (code "132") (name "unconnected-(D16A-I{slash}O-PadN10)") (class "Default")
      (node (ref "D16") (pin "N10") (pinfunction "I/O_N10") (pintype "bidirectional"))
    )
    (net (code "133") (name "unconnected-(D16A-I{slash}O-PadN11)") (class "Default")
      (node (ref "D16") (pin "N11") (pinfunction "I/O_N11") (pintype "bidirectional"))
    )
    (net (code "134") (name "unconnected-(D16A-I{slash}O-PadN13)") (class "Default")
      (node (ref "D16") (pin "N13") (pinfunction "I/O_N13") (pintype "bidirectional"))
    )
    (net (code "135") (name "unconnected-(D16A-I{slash}O-PadN14)") (class "Default")
      (node (ref "D16") (pin "N14") (pinfunction "I/O_N14") (pintype "bidirectional"))
    )
    (net (code "136") (name "unconnected-(D16A-I{slash}O-PadN15)") (class "Default")
      (node (ref "D16") (pin "N15") (pinfunction "I/O_N15") (pintype "bidirectional"))
    )
    (net (code "137") (name "unconnected-(D16A-I{slash}O-PadN16)") (class "Default")
      (node (ref "D16") (pin "N16") (pinfunction "I/O_N16") (pintype "bidirectional"))
    )
    (net (code "138") (name "unconnected-(D16A-I{slash}O-PadP4)") (class "Default")
      (node (ref "D16") (pin "P4") (pinfunction "I/O_P4") (pintype "bidirectional"))
    )
    (net (code "139") (name "unconnected-(D16A-I{slash}O-PadP6)") (class "Default")
      (node (ref "D16") (pin "P6") (pinfunction "I/O_P6") (pintype "bidirectional"))
    )
    (net (code "140") (name "unconnected-(D16A-I{slash}O-PadP7)") (class "Default")
      (node (ref "D16") (pin "P7") (pinfunction "I/O_P7") (pintype "bidirectional"))
    )
    (net (code "141") (name "unconnected-(D16A-I{slash}O-PadP8)") (class "Default")
      (node (ref "D16") (pin "P8") (pinfunction "I/O_P8") (pintype "bidirectional"))
    )
    (net (code "142") (name "unconnected-(D16A-I{slash}O-PadP10)") (class "Default")
      (node (ref "D16") (pin "P10") (pinfunction "I/O_P10") (pintype "bidirectional"))
    )
    (net (code "143") (name "unconnected-(D16A-I{slash}O-PadP13)") (class "Default")
      (node (ref "D16") (pin "P13") (pinfunction "I/O_P13") (pintype "bidirectional"))
    )
    (net (code "144") (name "unconnected-(D16A-I{slash}O-PadP14)") (class "Default")
      (node (ref "D16") (pin "P14") (pinfunction "I/O_P14") (pintype "bidirectional"))
    )
    (net (code "145") (name "unconnected-(D16A-I{slash}O-PadP15)") (class "Default")
      (node (ref "D16") (pin "P15") (pinfunction "I/O_P15") (pintype "bidirectional"))
    )
    (net (code "146") (name "unconnected-(D16A-I{slash}O-PadP16)") (class "Default")
      (node (ref "D16") (pin "P16") (pinfunction "I/O_P16") (pintype "bidirectional"))
    )
    (net (code "147") (name "unconnected-(D16A-I{slash}O-PadR3)") (class "Default")
      (node (ref "D16") (pin "R3") (pinfunction "I/O_R3") (pintype "bidirectional"))
    )
    (net (code "148") (name "unconnected-(D16A-I{slash}O-PadR5)") (class "Default")
      (node (ref "D16") (pin "R5") (pinfunction "I/O_R5") (pintype "bidirectional"))
    )
    (net (code "149") (name "unconnected-(D16A-I{slash}O-PadR6)") (class "Default")
      (node (ref "D16") (pin "R6") (pinfunction "I/O_R6") (pintype "bidirectional"))
    )
    (net (code "150") (name "unconnected-(D16A-I{slash}O-PadR7)") (class "Default")
      (node (ref "D16") (pin "R7") (pinfunction "I/O_R7") (pintype "bidirectional"))
    )
    (net (code "151") (name "unconnected-(D16A-I{slash}O-PadR8)") (class "Default")
      (node (ref "D16") (pin "R8") (pinfunction "I/O_R8") (pintype "bidirectional"))
    )
    (net (code "152") (name "unconnected-(D16A-I{slash}O-PadR9)") (class "Default")
      (node (ref "D16") (pin "R9") (pinfunction "I/O_R9") (pintype "bidirectional"))
    )
    (net (code "153") (name "unconnected-(D16A-I{slash}O-PadR10)") (class "Default")
      (node (ref "D16") (pin "R10") (pinfunction "I/O_R10") (pintype "bidirectional"))
    )
    (net (code "154") (name "unconnected-(D16A-I{slash}O-PadR12)") (class "Default")
      (node (ref "D16") (pin "R12") (pinfunction "I/O_R12") (pintype "bidirectional"))
    )
    (net (code "155") (name "unconnected-(D16A-I{slash}O-PadR13)") (class "Default")
      (node (ref "D16") (pin "R13") (pinfunction "I/O_R13") (pintype "bidirectional"))
    )
    (net (code "156") (name "unconnected-(D16A-I{slash}O-PadR14)") (class "Default")
      (node (ref "D16") (pin "R14") (pinfunction "I/O_R14") (pintype "bidirectional"))
    )
    (net (code "157") (name "unconnected-(D16A-I{slash}O-PadR15)") (class "Default")
      (node (ref "D16") (pin "R15") (pinfunction "I/O_R15") (pintype "bidirectional"))
    )
    (net (code "158") (name "unconnected-(D16A-I{slash}O-PadR16)") (class "Default")
      (node (ref "D16") (pin "R16") (pinfunction "I/O_R16") (pintype "bidirectional"))
    )
    (net (code "159") (name "unconnected-(D16A-I{slash}O-PadT5)") (class "Default")
      (node (ref "D16") (pin "T5") (pinfunction "I/O_T5") (pintype "bidirectional"))
    )
    (net (code "160") (name "unconnected-(D16A-I{slash}O-PadT7)") (class "Default")
      (node (ref "D16") (pin "T7") (pinfunction "I/O_T7") (pintype "bidirectional"))
    )
    (net (code "161") (name "unconnected-(D16A-I{slash}O-PadT8)") (class "Default")
      (node (ref "D16") (pin "T8") (pinfunction "I/O_T8") (pintype "bidirectional"))
    )
    (net (code "162") (name "unconnected-(D16A-I{slash}O-PadT10)") (class "Default")
      (node (ref "D16") (pin "T10") (pinfunction "I/O_T10") (pintype "bidirectional"))
    )
    (net (code "163") (name "unconnected-(D16A-I{slash}O-PadT15)") (class "Default")
      (node (ref "D16") (pin "T15") (pinfunction "I/O_T15") (pintype "bidirectional"))
    )
    (net (code "164") (name "unconnected-(D16A-I{slash}O-PadT16)") (class "Default")
      (node (ref "D16") (pin "T16") (pinfunction "I/O_T16") (pintype "bidirectional"))
    )
    (net (code "165") (name "unconnected-(D16B-I{slash}O,GSR-PadC4)") (class "Default")
      (node (ref "D16") (pin "C4") (pinfunction "I/O,GSR_C4") (pintype "bidirectional"))
    )
    (net (code "166") (name "unconnected-(D16B-I{slash}O,GTS0-PadD4)") (class "Default")
      (node (ref "D16") (pin "D4") (pinfunction "I/O,GTS0_D4") (pintype "bidirectional"))
    )
    (net (code "167") (name "unconnected-(D16B-I{slash}O,GTS1-PadE5)") (class "Default")
      (node (ref "D16") (pin "E5") (pinfunction "I/O,GTS1_E5") (pintype "bidirectional"))
    )
    (net (code "168") (name "unconnected-(D16B-I{slash}O,GTS2-PadD3)") (class "Default")
      (node (ref "D16") (pin "D3") (pinfunction "I/O,GTS2_D3") (pintype "bidirectional"))
    )
    (net (code "169") (name "unconnected-(D16B-I{slash}O,GTS3-PadE3)") (class "Default")
      (node (ref "D16") (pin "E3") (pinfunction "I/O,GTS3_E3") (pintype "bidirectional"))
    )
    (net (code "170") (name "unconnected-(D16B-I{slash}O-PadA2)") (class "Default")
      (node (ref "D16") (pin "A2") (pinfunction "I/O_A2") (pintype "bidirectional"))
    )
    (net (code "171") (name "unconnected-(D16B-I{slash}O-PadA3)") (class "Default")
      (node (ref "D16") (pin "A3") (pinfunction "I/O_A3") (pintype "bidirectional"))
    )
    (net (code "172") (name "unconnected-(D16B-I{slash}O-PadA4)") (class "Default")
      (node (ref "D16") (pin "A4") (pinfunction "I/O_A4") (pintype "bidirectional"))
    )
    (net (code "173") (name "unconnected-(D16B-I{slash}O-PadA5)") (class "Default")
      (node (ref "D16") (pin "A5") (pinfunction "I/O_A5") (pintype "bidirectional"))
    )
    (net (code "174") (name "unconnected-(D16B-I{slash}O-PadA6)") (class "Default")
      (node (ref "D16") (pin "A6") (pinfunction "I/O_A6") (pintype "bidirectional"))
    )
    (net (code "175") (name "unconnected-(D16B-I{slash}O-PadA7)") (class "Default")
      (node (ref "D16") (pin "A7") (pinfunction "I/O_A7") (pintype "bidirectional"))
    )
    (net (code "176") (name "unconnected-(D16B-I{slash}O-PadA9)") (class "Default")
      (node (ref "D16") (pin "A9") (pinfunction "I/O_A9") (pintype "bidirectional"))
    )
    (net (code "177") (name "unconnected-(D16B-I{slash}O-PadA13)") (class "Default")
      (node (ref "D16") (pin "A13") (pinfunction "I/O_A13") (pintype "bidirectional"))
    )
    (net (code "178") (name "unconnected-(D16B-I{slash}O-PadA14)") (class "Default")
      (node (ref "D16") (pin "A14") (pinfunction "I/O_A14") (pintype "bidirectional"))
    )
    (net (code "179") (name "unconnected-(D16B-I{slash}O-PadB3)") (class "Default")
      (node (ref "D16") (pin "B3") (pinfunction "I/O_B3") (pintype "bidirectional"))
    )
    (net (code "180") (name "unconnected-(D16B-I{slash}O-PadB4)") (class "Default")
      (node (ref "D16") (pin "B4") (pinfunction "I/O_B4") (pintype "bidirectional"))
    )
    (net (code "181") (name "unconnected-(D16B-I{slash}O-PadB5)") (class "Default")
      (node (ref "D16") (pin "B5") (pinfunction "I/O_B5") (pintype "bidirectional"))
    )
    (net (code "182") (name "unconnected-(D16B-I{slash}O-PadB9)") (class "Default")
      (node (ref "D16") (pin "B9") (pinfunction "I/O_B9") (pintype "bidirectional"))
    )
    (net (code "183") (name "unconnected-(D16B-I{slash}O-PadB10)") (class "Default")
      (node (ref "D16") (pin "B10") (pinfunction "I/O_B10") (pintype "bidirectional"))
    )
    (net (code "184") (name "unconnected-(D16B-I{slash}O-PadB13)") (class "Default")
      (node (ref "D16") (pin "B13") (pinfunction "I/O_B13") (pintype "bidirectional"))
    )
    (net (code "185") (name "unconnected-(D16B-I{slash}O-PadC3)") (class "Default")
      (node (ref "D16") (pin "C3") (pinfunction "I/O_C3") (pintype "bidirectional"))
    )
    (net (code "186") (name "unconnected-(D16B-I{slash}O-PadC7)") (class "Default")
      (node (ref "D16") (pin "C7") (pinfunction "I/O_C7") (pintype "bidirectional"))
    )
    (net (code "187") (name "unconnected-(D16B-I{slash}O-PadC8)") (class "Default")
      (node (ref "D16") (pin "C8") (pinfunction "I/O_C8") (pintype "bidirectional"))
    )
    (net (code "188") (name "unconnected-(D16B-I{slash}O-PadC9)") (class "Default")
      (node (ref "D16") (pin "C9") (pinfunction "I/O_C9") (pintype "bidirectional"))
    )
    (net (code "189") (name "unconnected-(D16B-I{slash}O-PadC10)") (class "Default")
      (node (ref "D16") (pin "C10") (pinfunction "I/O_C10") (pintype "bidirectional"))
    )
    (net (code "190") (name "unconnected-(D16B-I{slash}O-PadC11)") (class "Default")
      (node (ref "D16") (pin "C11") (pinfunction "I/O_C11") (pintype "bidirectional"))
    )
    (net (code "191") (name "unconnected-(D16B-I{slash}O-PadC12)") (class "Default")
      (node (ref "D16") (pin "C12") (pinfunction "I/O_C12") (pintype "bidirectional"))
    )
    (net (code "192") (name "unconnected-(D16B-I{slash}O-PadC13)") (class "Default")
      (node (ref "D16") (pin "C13") (pinfunction "I/O_C13") (pintype "bidirectional"))
    )
    (net (code "193") (name "unconnected-(D16B-I{slash}O-PadC14)") (class "Default")
      (node (ref "D16") (pin "C14") (pinfunction "I/O_C14") (pintype "bidirectional"))
    )
    (net (code "194") (name "unconnected-(D16B-I{slash}O-PadD7)") (class "Default")
      (node (ref "D16") (pin "D7") (pinfunction "I/O_D7") (pintype "bidirectional"))
    )
    (net (code "195") (name "unconnected-(D16B-I{slash}O-PadD8)") (class "Default")
      (node (ref "D16") (pin "D8") (pinfunction "I/O_D8") (pintype "bidirectional"))
    )
    (net (code "196") (name "unconnected-(D16B-I{slash}O-PadD9)") (class "Default")
      (node (ref "D16") (pin "D9") (pinfunction "I/O_D9") (pintype "bidirectional"))
    )
    (net (code "197") (name "unconnected-(D16B-I{slash}O-PadD10)") (class "Default")
      (node (ref "D16") (pin "D10") (pinfunction "I/O_D10") (pintype "bidirectional"))
    )
    (net (code "198") (name "unconnected-(D16B-I{slash}O-PadD11)") (class "Default")
      (node (ref "D16") (pin "D11") (pinfunction "I/O_D11") (pintype "bidirectional"))
    )
    (net (code "199") (name "unconnected-(D16B-I{slash}O-PadD13)") (class "Default")
      (node (ref "D16") (pin "D13") (pinfunction "I/O_D13") (pintype "bidirectional"))
    )
    (net (code "200") (name "unconnected-(D16B-I{slash}O-PadD15)") (class "Default")
      (node (ref "D16") (pin "D15") (pinfunction "I/O_D15") (pintype "bidirectional"))
    )
    (net (code "201") (name "unconnected-(D16B-I{slash}O-PadE4)") (class "Default")
      (node (ref "D16") (pin "E4") (pinfunction "I/O_E4") (pintype "bidirectional"))
    )
    (net (code "202") (name "unconnected-(D16B-I{slash}O-PadE8)") (class "Default")
      (node (ref "D16") (pin "E8") (pinfunction "I/O_E8") (pintype "bidirectional"))
    )
    (net (code "203") (name "unconnected-(D16B-I{slash}O-PadE9)") (class "Default")
      (node (ref "D16") (pin "E9") (pinfunction "I/O_E9") (pintype "bidirectional"))
    )
    (net (code "204") (name "unconnected-(D16B-I{slash}O-PadE10)") (class "Default")
      (node (ref "D16") (pin "E10") (pinfunction "I/O_E10") (pintype "bidirectional"))
    )
    (net (code "205") (name "unconnected-(D16B-I{slash}O-PadE11)") (class "Default")
      (node (ref "D16") (pin "E11") (pinfunction "I/O_E11") (pintype "bidirectional"))
    )
    (net (code "206") (name "unconnected-(D16B-I{slash}O-PadE12)") (class "Default")
      (node (ref "D16") (pin "E12") (pinfunction "I/O_E12") (pintype "bidirectional"))
    )
    (net (code "207") (name "unconnected-(D16B-I{slash}O-PadE13)") (class "Default")
      (node (ref "D16") (pin "E13") (pinfunction "I/O_E13") (pintype "bidirectional"))
    )
    (net (code "208") (name "unconnected-(D16B-I{slash}O-PadE14)") (class "Default")
      (node (ref "D16") (pin "E14") (pinfunction "I/O_E14") (pintype "bidirectional"))
    )
    (net (code "209") (name "unconnected-(D16B-I{slash}O-PadE15)") (class "Default")
      (node (ref "D16") (pin "E15") (pinfunction "I/O_E15") (pintype "bidirectional"))
    )
    (net (code "210") (name "unconnected-(D16B-I{slash}O-PadE16)") (class "Default")
      (node (ref "D16") (pin "E16") (pinfunction "I/O_E16") (pintype "bidirectional"))
    )
    (net (code "211") (name "unconnected-(D16B-I{slash}O-PadF5)") (class "Default")
      (node (ref "D16") (pin "F5") (pinfunction "I/O_F5") (pintype "bidirectional"))
    )
    (net (code "212") (name "unconnected-(D16B-I{slash}O-PadF12)") (class "Default")
      (node (ref "D16") (pin "F12") (pinfunction "I/O_F12") (pintype "bidirectional"))
    )
    (net (code "213") (name "unconnected-(D16B-I{slash}O-PadF13)") (class "Default")
      (node (ref "D16") (pin "F13") (pinfunction "I/O_F13") (pintype "bidirectional"))
    )
    (net (code "214") (name "unconnected-(D16B-I{slash}O-PadF14)") (class "Default")
      (node (ref "D16") (pin "F14") (pinfunction "I/O_F14") (pintype "bidirectional"))
    )
    (net (code "215") (name "unconnected-(D16B-I{slash}O-PadF15)") (class "Default")
      (node (ref "D16") (pin "F15") (pinfunction "I/O_F15") (pintype "bidirectional"))
    )
    (net (code "216") (name "unconnected-(D16B-I{slash}O-PadF16)") (class "Default")
      (node (ref "D16") (pin "F16") (pinfunction "I/O_F16") (pintype "bidirectional"))
    )
    (net (code "217") (name "unconnected-(D16B-I{slash}O-PadG4)") (class "Default")
      (node (ref "D16") (pin "G4") (pinfunction "I/O_G4") (pintype "bidirectional"))
    )
    (net (code "218") (name "unconnected-(D16B-I{slash}O-PadG5)") (class "Default")
      (node (ref "D16") (pin "G5") (pinfunction "I/O_G5") (pintype "bidirectional"))
    )
    (net (code "219") (name "unconnected-(D16B-I{slash}O-PadG11)") (class "Default")
      (node (ref "D16") (pin "G11") (pinfunction "I/O_G11") (pintype "bidirectional"))
    )
    (net (code "220") (name "unconnected-(D16B-I{slash}O-PadG13)") (class "Default")
      (node (ref "D16") (pin "G13") (pinfunction "I/O_G13") (pintype "bidirectional"))
    )
    (net (code "221") (name "unconnected-(D16B-I{slash}O-PadG14)") (class "Default")
      (node (ref "D16") (pin "G14") (pinfunction "I/O_G14") (pintype "bidirectional"))
    )
    (net (code "222") (name "unconnected-(D16B-I{slash}O-PadG15)") (class "Default")
      (node (ref "D16") (pin "G15") (pinfunction "I/O_G15") (pintype "bidirectional"))
    )
    (net (code "223") (name "unconnected-(D16B-I{slash}O-PadG16)") (class "Default")
      (node (ref "D16") (pin "G16") (pinfunction "I/O_G16") (pintype "bidirectional"))
    )
    (net (code "224") (name "unconnected-(D16B-I{slash}O-PadH3)") (class "Default")
      (node (ref "D16") (pin "H3") (pinfunction "I/O_H3") (pintype "bidirectional"))
    )
    (net (code "225") (name "unconnected-(D16B-I{slash}O-PadH4)") (class "Default")
      (node (ref "D16") (pin "H4") (pinfunction "I/O_H4") (pintype "bidirectional"))
    )
    (net (code "226") (name "unconnected-(D16B-I{slash}O-PadH5)") (class "Default")
      (node (ref "D16") (pin "H5") (pinfunction "I/O_H5") (pintype "bidirectional"))
    )
    (net (code "227") (name "unconnected-(D16B-I{slash}O-PadH12)") (class "Default")
      (node (ref "D16") (pin "H12") (pinfunction "I/O_H12") (pintype "bidirectional"))
    )
    (net (code "228") (name "unconnected-(D16B-I{slash}O-PadH13)") (class "Default")
      (node (ref "D16") (pin "H13") (pinfunction "I/O_H13") (pintype "bidirectional"))
    )
    (net (code "229") (name "unconnected-(D16B-I{slash}O-PadH14)") (class "Default")
      (node (ref "D16") (pin "H14") (pinfunction "I/O_H14") (pintype "bidirectional"))
    )
    (net (code "230") (name "unconnected-(D16B-I{slash}O-PadH15)") (class "Default")
      (node (ref "D16") (pin "H15") (pinfunction "I/O_H15") (pintype "bidirectional"))
    )
    (net (code "231") (name "unconnected-(D16B-I{slash}O-PadH16)") (class "Default")
      (node (ref "D16") (pin "H16") (pinfunction "I/O_H16") (pintype "bidirectional"))
    )
    (net (code "232") (name "unconnected-(D16B-I{slash}O-PadJ12)") (class "Default")
      (node (ref "D16") (pin "J12") (pinfunction "I/O_J12") (pintype "bidirectional"))
    )
    (net (code "233") (name "unconnected-(D16F-NC-PadA1)") (class "Default")
      (node (ref "D16") (pin "A1") (pinfunction "NC_A1") (pintype "passive+no_connect"))
    )
    (net (code "234") (name "unconnected-(D16F-NC-PadC2)") (class "Default")
      (node (ref "D16") (pin "C2") (pinfunction "NC_C2") (pintype "passive+no_connect"))
    )
    (net (code "235") (name "unconnected-(D16F-NC-PadC5)") (class "Default")
      (node (ref "D16") (pin "C5") (pinfunction "NC_C5") (pintype "passive+no_connect"))
    )
    (net (code "236") (name "unconnected-(D16F-NC-PadC6)") (class "Default")
      (node (ref "D16") (pin "C6") (pinfunction "NC_C6") (pintype "passive+no_connect"))
    )
    (net (code "237") (name "unconnected-(D16F-NC-PadC15)") (class "Default")
      (node (ref "D16") (pin "C15") (pinfunction "NC_C15") (pintype "passive+no_connect"))
    )
    (net (code "238") (name "unconnected-(D16F-NC-PadD1)") (class "Default")
      (node (ref "D16") (pin "D1") (pinfunction "NC_D1") (pintype "passive+no_connect"))
    )
    (net (code "239") (name "unconnected-(D16F-NC-PadD6)") (class "Default")
      (node (ref "D16") (pin "D6") (pinfunction "NC_D6") (pintype "passive+no_connect"))
    )
    (net (code "240") (name "unconnected-(D16F-NC-PadD14)") (class "Default")
      (node (ref "D16") (pin "D14") (pinfunction "NC_D14") (pintype "passive+no_connect"))
    )
    (net (code "241") (name "unconnected-(D16F-NC-PadD16)") (class "Default")
      (node (ref "D16") (pin "D16") (pinfunction "NC_D16") (pintype "passive+no_connect"))
    )
    (net (code "242") (name "unconnected-(D16F-NC-PadE1)") (class "Default")
      (node (ref "D16") (pin "E1") (pinfunction "NC_E1") (pintype "passive+no_connect"))
    )
    (net (code "243") (name "unconnected-(D16F-NC-PadE6)") (class "Default")
      (node (ref "D16") (pin "E6") (pinfunction "NC_E6") (pintype "passive+no_connect"))
    )
    (net (code "244") (name "unconnected-(D16F-NC-PadE7)") (class "Default")
      (node (ref "D16") (pin "E7") (pinfunction "NC_E7") (pintype "passive+no_connect"))
    )
    (net (code "245") (name "unconnected-(D16F-NC-PadF1)") (class "Default")
      (node (ref "D16") (pin "F1") (pinfunction "NC_F1") (pintype "passive+no_connect"))
    )
    (net (code "246") (name "unconnected-(D16F-NC-PadG1)") (class "Default")
      (node (ref "D16") (pin "G1") (pinfunction "NC_G1") (pintype "passive+no_connect"))
    )
    (net (code "247") (name "unconnected-(D16F-NC-PadG2)") (class "Default")
      (node (ref "D16") (pin "G2") (pinfunction "NC_G2") (pintype "passive+no_connect"))
    )
    (net (code "248") (name "unconnected-(D16F-NC-PadG12)") (class "Default")
      (node (ref "D16") (pin "G12") (pinfunction "NC_G12") (pintype "passive+no_connect"))
    )
    (net (code "249") (name "unconnected-(D16F-NC-PadJ16)") (class "Default")
      (node (ref "D16") (pin "J16") (pinfunction "NC_J16") (pintype "passive+no_connect"))
    )
    (net (code "250") (name "unconnected-(D16F-NC-PadK12)") (class "Default")
      (node (ref "D16") (pin "K12") (pinfunction "NC_K12") (pintype "passive+no_connect"))
    )
    (net (code "251") (name "unconnected-(D16F-NC-PadM4)") (class "Default")
      (node (ref "D16") (pin "M4") (pinfunction "NC_M4") (pintype "passive+no_connect"))
    )
    (net (code "252") (name "unconnected-(D16F-NC-PadM9)") (class "Default")
      (node (ref "D16") (pin "M9") (pinfunction "NC_M9") (pintype "passive+no_connect"))
    )
    (net (code "253") (name "unconnected-(D16F-NC-PadM10)") (class "Default")
      (node (ref "D16") (pin "M10") (pinfunction "NC_M10") (pintype "passive+no_connect"))
    )
    (net (code "254") (name "unconnected-(D16F-NC-PadP9)") (class "Default")
      (node (ref "D16") (pin "P9") (pinfunction "NC_P9") (pintype "passive+no_connect"))
    )
    (net (code "255") (name "unconnected-(D16F-NC-PadP11)") (class "Default")
      (node (ref "D16") (pin "P11") (pinfunction "NC_P11") (pintype "passive+no_connect"))
    )
    (net (code "256") (name "unconnected-(D16F-NC-PadT9)") (class "Default")
      (node (ref "D16") (pin "T9") (pinfunction "NC_T9") (pintype "passive+no_connect"))
    )
    (net (code "257") (name "unconnected-(D16F-NC-PadT11)") (class "Default")
      (node (ref "D16") (pin "T11") (pinfunction "NC_T11") (pintype "passive+no_connect"))
    )
    (net (code "258") (name "unconnected-(D16F-NC-PadT12)") (class "Default")
      (node (ref "D16") (pin "T12") (pinfunction "NC_T12") (pintype "passive+no_connect"))
    )
    (net (code "259") (name "unconnected-(D16F-NC-PadT13)") (class "Default")
      (node (ref "D16") (pin "T13") (pinfunction "NC_T13") (pintype "passive+no_connect"))
    )
    (net (code "260") (name "unconnected-(D16F-NC-PadT14)") (class "Default")
      (node (ref "D16") (pin "T14") (pinfunction "NC_T14") (pintype "passive+no_connect"))
    )
    (net (code "261") (name "unconnected-(R80-Pad1)") (class "Default")
      (node (ref "R80") (pin "1") (pinfunction "1_1") (pintype "passive"))
    )
    (net (code "262") (name "unconnected-(R80-Pad8)") (class "Default")
      (node (ref "R80") (pin "8") (pinfunction "8_8") (pintype "passive"))
    )
    (net (code "263") (name "unconnected-(R89-Pad4)") (class "Default")
      (node (ref "R89") (pin "4") (pinfunction "4_4") (pintype "passive"))
    )
    (net (code "264") (name "unconnected-(R89-Pad5)") (class "Default")
      (node (ref "R89") (pin "5") (pinfunction "5_5") (pintype "passive"))
    )
    (net (code "265") (name "unconnected-(R91-Pad1)") (class "Default")
      (node (ref "R91") (pin "1") (pinfunction "1_1") (pintype "passive"))
    )
    (net (code "266") (name "unconnected-(R91-Pad8)") (class "Default")
      (node (ref "R91") (pin "8") (pinfunction "8_8") (pintype "passive"))
    )
    (net (code "267") (name "unconnected-(X3-Pad12)") (class "Default")
      (node (ref "X3") (pin "12") (pinfunction "12_12") (pintype "passive+no_connect"))
    )
    (net (code "268") (name "unconnected-(X3-Pad14)") (class "Default")
      (node (ref "X3") (pin "14") (pinfunction "14_14") (pintype "passive+no_connect"))
    )
  )
)
